# P06_LED_Config_Button.net
KiCad netlist of a schematic drawn in Altium Designer
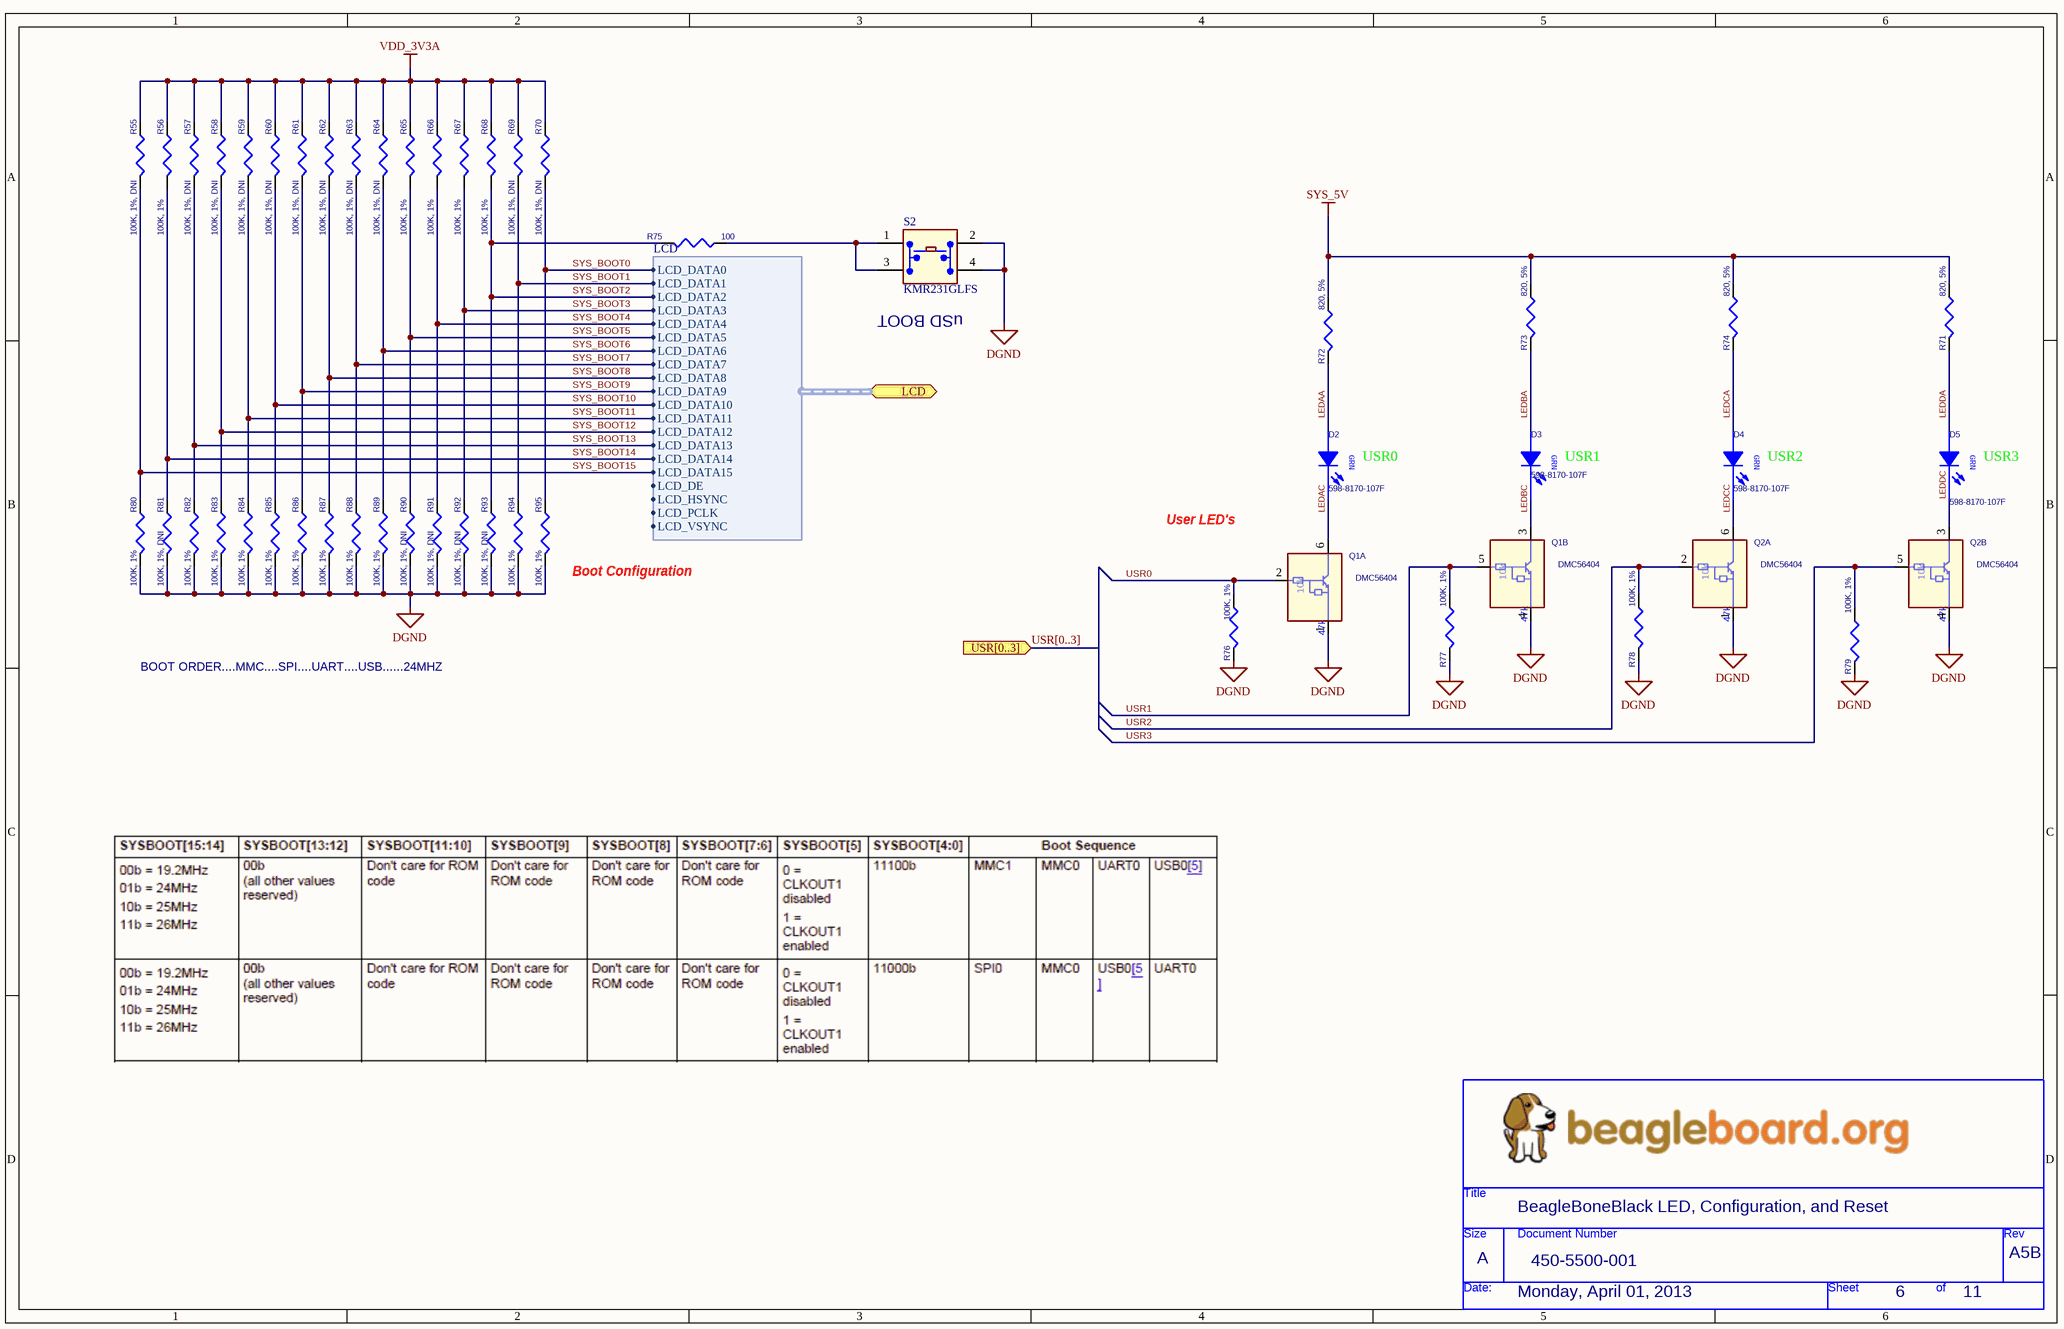
[diagram p0: P06_LED, Config, & Button.SchDoc]

(export (version "E")
  (design (tool "Eeschema 10.0.6"))
  (components
    (comp (ref "D2")
      (value "598-8170-107F")
      (footprint "LED_0603")
      (description "LED GREEN CLEAR 0805 SMD")
      (fields
        (field (name "MANUFACTURER") "Lite-On Inc")
        (field (name "MANUFACTURER PART NUMBER") "LTST-C170KGKT")
      )
      (libsource (lib "BEAGLEBONEBLACK_REV A5B") (part "LED_LTST-C150GKT"))
    )
    (comp (ref "D3")
      (value "598-8170-107F")
      (footprint "LED_0603")
      (description "LED GREEN CLEAR 0805 SMD")
      (fields
        (field (name "MANUFACTURER") "Lite-On Inc")
        (field (name "MANUFACTURER PART NUMBER") "LTST-C170KGKT")
      )
      (libsource (lib "BEAGLEBONEBLACK_REV A5B") (part "LED_LTST-C150GKT"))
    )
    (comp (ref "D4")
      (value "598-8170-107F")
      (footprint "LED_0603")
      (description "LED GREEN CLEAR 0805 SMD")
      (fields
        (field (name "MANUFACTURER") "Lite-On Inc")
        (field (name "MANUFACTURER PART NUMBER") "LTST-C170KGKT")
      )
      (libsource (lib "BEAGLEBONEBLACK_REV A5B") (part "LED_LTST-C150GKT"))
    )
    (comp (ref "D5")
      (value "598-8170-107F")
      (footprint "LED_0603")
      (description "LED GREEN CLEAR 0805 SMD")
      (fields
        (field (name "MANUFACTURER") "Lite-On Inc")
        (field (name "MANUFACTURER PART NUMBER") "LTST-C170KGKT")
      )
      (libsource (lib "BEAGLEBONEBLACK_REV A5B") (part "LED_LTST-C150GKT"))
    )
    (comp (ref "Q1")
      (value "DMC56404")
      (description "TRANS PREBIASED DUAL NPN SOT363")
      (fields
        (field (name "MANUFACTURER") "Toshiba")
        (field (name "MANUFACTURER PART NUMBER") "DDC114YU-7-F")
      )
      (libsource (lib "BEAGLEBONEBLACK_REV A5B") (part "RN1907"))
    )
    (comp (ref "Q2")
      (value "DMC56404")
      (description "TRANS PREBIASED DUAL NPN SOT363")
      (fields
        (field (name "MANUFACTURER") "Toshiba")
        (field (name "MANUFACTURER PART NUMBER") "DDC114YU-7-F")
      )
      (libsource (lib "BEAGLEBONEBLACK_REV A5B") (part "RN1907"))
    )
    (comp (ref "R55")
      (value "100K, 1%, DNI")
      (footprint "402")
      (description "RES 100K OHM 1/16W 1% 0402 SMD")
      (fields
        (field (name "MANUFACTURER") "Stackpole Electronics Inc")
        (field (name "MANUFACTURER PART NUMBER") "RMCF0402FT100K")
      )
      (libsource (lib "BEAGLEBONEBLACK_REV A5B") (part "RES_100K_1/16W_1%_0402"))
    )
    (comp (ref "R56")
      (value "100K, 1%")
      (footprint "402")
      (description "RES 100K OHM 1/16W 1% 0402 SMD")
      (fields
        (field (name "MANUFACTURER") "Stackpole Electronics Inc")
        (field (name "MANUFACTURER PART NUMBER") "RMCF0402FT100K")
      )
      (libsource (lib "BEAGLEBONEBLACK_REV A5B") (part "RES_100K_1/16W_1%_0402"))
    )
    (comp (ref "R57")
      (value "100K, 1%, DNI")
      (footprint "402")
      (description "RES 100K OHM 1/16W 1% 0402 SMD")
      (fields
        (field (name "MANUFACTURER") "Stackpole Electronics Inc")
        (field (name "MANUFACTURER PART NUMBER") "RMCF0402FT100K")
      )
      (libsource (lib "BEAGLEBONEBLACK_REV A5B") (part "RES_100K_1/16W_1%_0402"))
    )
    (comp (ref "R58")
      (value "100K, 1%, DNI")
      (footprint "402")
      (description "RES 100K OHM 1/16W 1% 0402 SMD")
      (fields
        (field (name "MANUFACTURER") "Stackpole Electronics Inc")
        (field (name "MANUFACTURER PART NUMBER") "RMCF0402FT100K")
      )
      (libsource (lib "BEAGLEBONEBLACK_REV A5B") (part "RES_100K_1/16W_1%_0402"))
    )
    (comp (ref "R59")
      (value "100K, 1%, DNI")
      (footprint "402")
      (description "RES 100K OHM 1/16W 1% 0402 SMD")
      (fields
        (field (name "MANUFACTURER") "Stackpole Electronics Inc")
        (field (name "MANUFACTURER PART NUMBER") "RMCF0402FT100K")
      )
      (libsource (lib "BEAGLEBONEBLACK_REV A5B") (part "RES_100K_1/16W_1%_0402"))
    )
    (comp (ref "R60")
      (value "100K, 1%, DNI")
      (footprint "402")
      (description "RES 100K OHM 1/16W 1% 0402 SMD")
      (fields
        (field (name "MANUFACTURER") "Stackpole Electronics Inc")
        (field (name "MANUFACTURER PART NUMBER") "RMCF0402FT100K")
      )
      (libsource (lib "BEAGLEBONEBLACK_REV A5B") (part "RES_100K_1/16W_1%_0402"))
    )
    (comp (ref "R61")
      (value "100K, 1%, DNI")
      (footprint "402")
      (description "RES 100K OHM 1/16W 1% 0402 SMD")
      (fields
        (field (name "MANUFACTURER") "Stackpole Electronics Inc")
        (field (name "MANUFACTURER PART NUMBER") "RMCF0402FT100K")
      )
      (libsource (lib "BEAGLEBONEBLACK_REV A5B") (part "RES_100K_1/16W_1%_0402"))
    )
    (comp (ref "R62")
      (value "100K, 1%, DNI")
      (footprint "402")
      (description "RES 100K OHM 1/16W 1% 0402 SMD")
      (fields
        (field (name "MANUFACTURER") "Stackpole Electronics Inc")
        (field (name "MANUFACTURER PART NUMBER") "RMCF0402FT100K")
      )
      (libsource (lib "BEAGLEBONEBLACK_REV A5B") (part "RES_100K_1/16W_1%_0402"))
    )
    (comp (ref "R63")
      (value "100K, 1%, DNI")
      (footprint "402")
      (description "RES 100K OHM 1/16W 1% 0402 SMD")
      (fields
        (field (name "MANUFACTURER") "Stackpole Electronics Inc")
        (field (name "MANUFACTURER PART NUMBER") "RMCF0402FT100K")
      )
      (libsource (lib "BEAGLEBONEBLACK_REV A5B") (part "RES_100K_1/16W_1%_0402"))
    )
    (comp (ref "R64")
      (value "100K, 1%, DNI")
      (footprint "402")
      (description "RES 100K OHM 1/16W 1% 0402 SMD")
      (fields
        (field (name "MANUFACTURER") "Stackpole Electronics Inc")
        (field (name "MANUFACTURER PART NUMBER") "RMCF0402FT100K")
      )
      (libsource (lib "BEAGLEBONEBLACK_REV A5B") (part "RES_100K_1/16W_1%_0402"))
    )
    (comp (ref "R65")
      (value "100K, 1%")
      (footprint "402")
      (description "RES 100K OHM 1/16W 1% 0402 SMD")
      (fields
        (field (name "MANUFACTURER") "Stackpole Electronics Inc")
        (field (name "MANUFACTURER PART NUMBER") "RMCF0402FT100K")
      )
      (libsource (lib "BEAGLEBONEBLACK_REV A5B") (part "RES_100K_1/16W_1%_0402"))
    )
    (comp (ref "R66")
      (value "100K, 1%")
      (footprint "402")
      (description "RES 100K OHM 1/16W 1% 0402 SMD")
      (fields
        (field (name "MANUFACTURER") "Stackpole Electronics Inc")
        (field (name "MANUFACTURER PART NUMBER") "RMCF0402FT100K")
      )
      (libsource (lib "BEAGLEBONEBLACK_REV A5B") (part "RES_100K_1/16W_1%_0402"))
    )
    (comp (ref "R67")
      (value "100K, 1%")
      (footprint "402")
      (description "RES 100K OHM 1/16W 1% 0402 SMD")
      (fields
        (field (name "MANUFACTURER") "Stackpole Electronics Inc")
        (field (name "MANUFACTURER PART NUMBER") "RMCF0402FT100K")
      )
      (libsource (lib "BEAGLEBONEBLACK_REV A5B") (part "RES_100K_1/16W_1%_0402"))
    )
    (comp (ref "R68")
      (value "100K, 1%")
      (footprint "402")
      (description "RES 100K OHM 1/16W 1% 0402 SMD")
      (fields
        (field (name "MANUFACTURER") "Stackpole Electronics Inc")
        (field (name "MANUFACTURER PART NUMBER") "RMCF0402FT100K")
      )
      (libsource (lib "BEAGLEBONEBLACK_REV A5B") (part "RES_100K_1/16W_1%_0402"))
    )
    (comp (ref "R69")
      (value "100K, 1%, DNI")
      (footprint "402")
      (description "RES 100K OHM 1/16W 1% 0402 SMD")
      (fields
        (field (name "MANUFACTURER") "Stackpole Electronics Inc")
        (field (name "MANUFACTURER PART NUMBER") "RMCF0402FT100K")
      )
      (libsource (lib "BEAGLEBONEBLACK_REV A5B") (part "RES_100K_1/16W_1%_0402"))
    )
    (comp (ref "R70")
      (value "100K, 1%, DNI")
      (footprint "402")
      (description "RES 100K OHM 1/16W 1% 0402 SMD")
      (fields
        (field (name "MANUFACTURER") "Stackpole Electronics Inc")
        (field (name "MANUFACTURER PART NUMBER") "RMCF0402FT100K")
      )
      (libsource (lib "BEAGLEBONEBLACK_REV A5B") (part "RES_100K_1/16W_1%_0402"))
    )
    (comp (ref "R71")
      (value "820, 5%")
      (footprint "402")
      (description "RES 820 OHM 1/10W 5% 0402 SMD")
      (fields
        (field (name "MANUFACTURER") "Yageo")
        (field (name "MANUFACTURER PART NUMBER") "RC0402JR-07820RL")
      )
      (libsource (lib "BEAGLEBONEBLACK_REV A5B") (part "RES_470_1/10W_5%_0402"))
    )
    (comp (ref "R72")
      (value "820, 5%")
      (footprint "402")
      (description "RES 820 OHM 1/10W 5% 0402 SMD")
      (fields
        (field (name "MANUFACTURER") "Yageo")
        (field (name "MANUFACTURER PART NUMBER") "RC0402JR-07820RL")
      )
      (libsource (lib "BEAGLEBONEBLACK_REV A5B") (part "RES_470_1/10W_5%_0402"))
    )
    (comp (ref "R73")
      (value "820, 5%")
      (footprint "402")
      (description "RES 820 OHM 1/10W 5% 0402 SMD")
      (fields
        (field (name "MANUFACTURER") "Yageo")
        (field (name "MANUFACTURER PART NUMBER") "RC0402JR-07820RL")
      )
      (libsource (lib "BEAGLEBONEBLACK_REV A5B") (part "RES_470_1/10W_5%_0402"))
    )
    (comp (ref "R74")
      (value "820, 5%")
      (footprint "402")
      (description "RES 820 OHM 1/10W 5% 0402 SMD")
      (fields
        (field (name "MANUFACTURER") "Yageo")
        (field (name "MANUFACTURER PART NUMBER") "RC0402JR-07820RL")
      )
      (libsource (lib "BEAGLEBONEBLACK_REV A5B") (part "RES_470_1/10W_5%_0402"))
    )
    (comp (ref "R75")
      (value "100")
      (footprint "402")
      (description "RES 100 OHM 1/10W 5% 0402 SMD")
      (fields
        (field (name "MANUFACTURER") "Panasonic Electronic Components")
        (field (name "MANUFACTURER PART NUMBER") "ERJ-2RKF1000X")
      )
      (libsource (lib "BEAGLEBONEBLACK_REV A5B") (part "RES SMD"))
    )
    (comp (ref "R76")
      (value "100K, 1%")
      (footprint "402")
      (description "RES 100K OHM 1/16W 1% 0402 SMD")
      (fields
        (field (name "MANUFACTURER") "Stackpole Electronics Inc")
        (field (name "MANUFACTURER PART NUMBER") "RMCF0402FT100K")
      )
      (libsource (lib "BEAGLEBONEBLACK_REV A5B") (part "RES_100K_1/16W_1%_0402"))
    )
    (comp (ref "R77")
      (value "100K, 1%")
      (footprint "402")
      (description "RES 100K OHM 1/16W 1% 0402 SMD")
      (fields
        (field (name "MANUFACTURER") "Stackpole Electronics Inc")
        (field (name "MANUFACTURER PART NUMBER") "RMCF0402FT100K")
      )
      (libsource (lib "BEAGLEBONEBLACK_REV A5B") (part "RES_100K_1/16W_1%_0402"))
    )
    (comp (ref "R78")
      (value "100K, 1%")
      (footprint "402")
      (description "RES 100K OHM 1/16W 1% 0402 SMD")
      (fields
        (field (name "MANUFACTURER") "Stackpole Electronics Inc")
        (field (name "MANUFACTURER PART NUMBER") "RMCF0402FT100K")
      )
      (libsource (lib "BEAGLEBONEBLACK_REV A5B") (part "RES_100K_1/16W_1%_0402"))
    )
    (comp (ref "R79")
      (value "100K, 1%")
      (footprint "402")
      (description "RES 100K OHM 1/16W 1% 0402 SMD")
      (fields
        (field (name "MANUFACTURER") "Stackpole Electronics Inc")
        (field (name "MANUFACTURER PART NUMBER") "RMCF0402FT100K")
      )
      (libsource (lib "BEAGLEBONEBLACK_REV A5B") (part "RES_100K_1/16W_1%_0402"))
    )
    (comp (ref "R80")
      (value "100K, 1%")
      (footprint "402")
      (description "RES 100K OHM 1/16W 1% 0402 SMD")
      (fields
        (field (name "MANUFACTURER") "Stackpole Electronics Inc")
        (field (name "MANUFACTURER PART NUMBER") "RMCF0402FT100K")
      )
      (libsource (lib "BEAGLEBONEBLACK_REV A5B") (part "RES_100K_1/16W_1%_0402"))
    )
    (comp (ref "R81")
      (value "100K, 1%, DNI")
      (footprint "402")
      (description "RES 100K OHM 1/16W 1% 0402 SMD")
      (fields
        (field (name "MANUFACTURER") "Stackpole Electronics Inc")
        (field (name "MANUFACTURER PART NUMBER") "RMCF0402FT100K")
      )
      (libsource (lib "BEAGLEBONEBLACK_REV A5B") (part "RES_100K_1/16W_1%_0402"))
    )
    (comp (ref "R82")
      (value "100K, 1%")
      (footprint "402")
      (description "RES 100K OHM 1/16W 1% 0402 SMD")
      (fields
        (field (name "MANUFACTURER") "Stackpole Electronics Inc")
        (field (name "MANUFACTURER PART NUMBER") "RMCF0402FT100K")
      )
      (libsource (lib "BEAGLEBONEBLACK_REV A5B") (part "RES_100K_1/16W_1%_0402"))
    )
    (comp (ref "R83")
      (value "100K, 1%")
      (footprint "402")
      (description "RES 100K OHM 1/16W 1% 0402 SMD")
      (fields
        (field (name "MANUFACTURER") "Stackpole Electronics Inc")
        (field (name "MANUFACTURER PART NUMBER") "RMCF0402FT100K")
      )
      (libsource (lib "BEAGLEBONEBLACK_REV A5B") (part "RES_100K_1/16W_1%_0402"))
    )
    (comp (ref "R84")
      (value "100K, 1%")
      (footprint "402")
      (description "RES 100K OHM 1/16W 1% 0402 SMD")
      (fields
        (field (name "MANUFACTURER") "Stackpole Electronics Inc")
        (field (name "MANUFACTURER PART NUMBER") "RMCF0402FT100K")
      )
      (libsource (lib "BEAGLEBONEBLACK_REV A5B") (part "RES_100K_1/16W_1%_0402"))
    )
    (comp (ref "R85")
      (value "100K, 1%")
      (footprint "402")
      (description "RES 100K OHM 1/16W 1% 0402 SMD")
      (fields
        (field (name "MANUFACTURER") "Stackpole Electronics Inc")
        (field (name "MANUFACTURER PART NUMBER") "RMCF0402FT100K")
      )
      (libsource (lib "BEAGLEBONEBLACK_REV A5B") (part "RES_100K_1/16W_1%_0402"))
    )
    (comp (ref "R86")
      (value "100K, 1%")
      (footprint "402")
      (description "RES 100K OHM 1/16W 1% 0402 SMD")
      (fields
        (field (name "MANUFACTURER") "Stackpole Electronics Inc")
        (field (name "MANUFACTURER PART NUMBER") "RMCF0402FT100K")
      )
      (libsource (lib "BEAGLEBONEBLACK_REV A5B") (part "RES_100K_1/16W_1%_0402"))
    )
    (comp (ref "R87")
      (value "100K, 1%")
      (footprint "402")
      (description "RES 100K OHM 1/16W 1% 0402 SMD")
      (fields
        (field (name "MANUFACTURER") "Stackpole Electronics Inc")
        (field (name "MANUFACTURER PART NUMBER") "RMCF0402FT100K")
      )
      (libsource (lib "BEAGLEBONEBLACK_REV A5B") (part "RES_100K_1/16W_1%_0402"))
    )
    (comp (ref "R88")
      (value "100K, 1%")
      (footprint "402")
      (description "RES 100K OHM 1/16W 1% 0402 SMD")
      (fields
        (field (name "MANUFACTURER") "Stackpole Electronics Inc")
        (field (name "MANUFACTURER PART NUMBER") "RMCF0402FT100K")
      )
      (libsource (lib "BEAGLEBONEBLACK_REV A5B") (part "RES_100K_1/16W_1%_0402"))
    )
    (comp (ref "R89")
      (value "100K, 1%")
      (footprint "402")
      (description "RES 100K OHM 1/16W 1% 0402 SMD")
      (fields
        (field (name "MANUFACTURER") "Stackpole Electronics Inc")
        (field (name "MANUFACTURER PART NUMBER") "RMCF0402FT100K")
      )
      (libsource (lib "BEAGLEBONEBLACK_REV A5B") (part "RES_100K_1/16W_1%_0402"))
    )
    (comp (ref "R90")
      (value "100K, 1%, DNI")
      (footprint "402")
      (description "RES 100K OHM 1/16W 1% 0402 SMD")
      (fields
        (field (name "MANUFACTURER") "Stackpole Electronics Inc")
        (field (name "MANUFACTURER PART NUMBER") "RMCF0402FT100K")
      )
      (libsource (lib "BEAGLEBONEBLACK_REV A5B") (part "RES_100K_1/16W_1%_0402"))
    )
    (comp (ref "R91")
      (value "100K, 1%, DNI")
      (footprint "402")
      (description "RES 100K OHM 1/16W 1% 0402 SMD")
      (fields
        (field (name "MANUFACTURER") "Stackpole Electronics Inc")
        (field (name "MANUFACTURER PART NUMBER") "RMCF0402FT100K")
      )
      (libsource (lib "BEAGLEBONEBLACK_REV A5B") (part "RES_100K_1/16W_1%_0402"))
    )
    (comp (ref "R92")
      (value "100K, 1%, DNI")
      (footprint "402")
      (description "RES 100K OHM 1/16W 1% 0402 SMD")
      (fields
        (field (name "MANUFACTURER") "Stackpole Electronics Inc")
        (field (name "MANUFACTURER PART NUMBER") "RMCF0402FT100K")
      )
      (libsource (lib "BEAGLEBONEBLACK_REV A5B") (part "RES_100K_1/16W_1%_0402"))
    )
    (comp (ref "R93")
      (value "100K, 1%, DNI")
      (footprint "402")
      (description "RES 100K OHM 1/16W 1% 0402 SMD")
      (fields
        (field (name "MANUFACTURER") "Stackpole Electronics Inc")
        (field (name "MANUFACTURER PART NUMBER") "RMCF0402FT100K")
      )
      (libsource (lib "BEAGLEBONEBLACK_REV A5B") (part "RES_100K_1/16W_1%_0402"))
    )
    (comp (ref "R94")
      (value "100K, 1%")
      (footprint "402")
      (description "RES 100K OHM 1/16W 1% 0402 SMD")
      (fields
        (field (name "MANUFACTURER") "Stackpole Electronics Inc")
        (field (name "MANUFACTURER PART NUMBER") "RMCF0402FT100K")
      )
      (libsource (lib "BEAGLEBONEBLACK_REV A5B") (part "RES_100K_1/16W_1%_0402"))
    )
    (comp (ref "R95")
      (value "100K, 1%")
      (footprint "402")
      (description "RES 100K OHM 1/16W 1% 0402 SMD")
      (fields
        (field (name "MANUFACTURER") "Stackpole Electronics Inc")
        (field (name "MANUFACTURER PART NUMBER") "RMCF0402FT100K")
      )
      (libsource (lib "BEAGLEBONEBLACK_REV A5B") (part "RES_100K_1/16W_1%_0402"))
    )
    (comp (ref "S2")
      (value "KMR231GLFS")
      (footprint "SW4SMD_63X161LS")
      (description "Microminiature Tact Switch for SMT")
      (fields (field (name "MANUFACTURER") "C&K Components"))
      (libsource (lib "BEAGLEBONEBLACK_REV A5B") (part "KMR2"))
    )
  )
  (nets
    (net (code "2") (name "/LEDAA") (class "Default")
      (node (ref "D2") (pin "2") (pinfunction "A_2") (pintype "passive"))
      (node (ref "R72") (pin "2") (pinfunction "2_2") (pintype "passive"))
    )
    (net (code "3") (name "/LEDAC") (class "Default")
      (node (ref "D2") (pin "1") (pinfunction "C_1") (pintype "passive"))
      (node (ref "Q1") (pin "6") (pinfunction "3_6") (pintype "passive"))
    )
    (net (code "4") (name "/LEDBA") (class "Default")
      (node (ref "D3") (pin "2") (pinfunction "A_2") (pintype "passive"))
      (node (ref "R73") (pin "2") (pinfunction "2_2") (pintype "passive"))
    )
    (net (code "5") (name "/LEDBC") (class "Default")
      (node (ref "D3") (pin "1") (pinfunction "C_1") (pintype "passive"))
      (node (ref "Q1") (pin "3") (pinfunction "3_3") (pintype "passive"))
    )
    (net (code "6") (name "/LEDCA") (class "Default")
      (node (ref "D4") (pin "2") (pinfunction "A_2") (pintype "passive"))
      (node (ref "R74") (pin "2") (pinfunction "2_2") (pintype "passive"))
    )
    (net (code "7") (name "/LEDCC") (class "Default")
      (node (ref "D4") (pin "1") (pinfunction "C_1") (pintype "passive"))
      (node (ref "Q2") (pin "6") (pinfunction "3_6") (pintype "passive"))
    )
    (net (code "8") (name "/LEDDA") (class "Default")
      (node (ref "D5") (pin "2") (pinfunction "A_2") (pintype "passive"))
      (node (ref "R71") (pin "2") (pinfunction "2_2") (pintype "passive"))
    )
    (net (code "9") (name "/LEDDC") (class "Default")
      (node (ref "D5") (pin "1") (pinfunction "C_1") (pintype "passive"))
      (node (ref "Q2") (pin "3") (pinfunction "3_3") (pintype "passive"))
    )
    (net (code "10") (name "/SYS_BOOT0") (class "Default")
      (node (ref "R70") (pin "2") (pinfunction "2_2") (pintype "passive"))
      (node (ref "R95") (pin "1") (pinfunction "1_1") (pintype "passive"))
    )
    (net (code "11") (name "/SYS_BOOT1") (class "Default")
      (node (ref "R69") (pin "2") (pinfunction "2_2") (pintype "passive"))
      (node (ref "R94") (pin "1") (pinfunction "1_1") (pintype "passive"))
    )
    (net (code "12") (name "/SYS_BOOT2") (class "Default")
      (node (ref "R68") (pin "2") (pinfunction "2_2") (pintype "passive"))
      (node (ref "R75") (pin "1") (pinfunction "P1_1") (pintype "passive"))
      (node (ref "R93") (pin "1") (pinfunction "1_1") (pintype "passive"))
    )
    (net (code "13") (name "/SYS_BOOT3") (class "Default")
      (node (ref "R67") (pin "2") (pinfunction "2_2") (pintype "passive"))
      (node (ref "R92") (pin "1") (pinfunction "1_1") (pintype "passive"))
    )
    (net (code "14") (name "/SYS_BOOT4") (class "Default")
      (node (ref "R66") (pin "2") (pinfunction "2_2") (pintype "passive"))
      (node (ref "R91") (pin "1") (pinfunction "1_1") (pintype "passive"))
    )
    (net (code "15") (name "/SYS_BOOT5") (class "Default")
      (node (ref "R65") (pin "2") (pinfunction "2_2") (pintype "passive"))
      (node (ref "R90") (pin "1") (pinfunction "1_1") (pintype "passive"))
    )
    (net (code "16") (name "/SYS_BOOT6") (class "Default")
      (node (ref "R64") (pin "2") (pinfunction "2_2") (pintype "passive"))
      (node (ref "R89") (pin "1") (pinfunction "1_1") (pintype "passive"))
    )
    (net (code "17") (name "/SYS_BOOT7") (class "Default")
      (node (ref "R63") (pin "2") (pinfunction "2_2") (pintype "passive"))
      (node (ref "R88") (pin "1") (pinfunction "1_1") (pintype "passive"))
    )
    (net (code "18") (name "/SYS_BOOT8") (class "Default")
      (node (ref "R62") (pin "2") (pinfunction "2_2") (pintype "passive"))
      (node (ref "R87") (pin "1") (pinfunction "1_1") (pintype "passive"))
    )
    (net (code "19") (name "/SYS_BOOT9") (class "Default")
      (node (ref "R61") (pin "2") (pinfunction "2_2") (pintype "passive"))
      (node (ref "R86") (pin "1") (pinfunction "1_1") (pintype "passive"))
    )
    (net (code "20") (name "/SYS_BOOT10") (class "Default")
      (node (ref "R60") (pin "2") (pinfunction "2_2") (pintype "passive"))
      (node (ref "R85") (pin "1") (pinfunction "1_1") (pintype "passive"))
    )
    (net (code "21") (name "/SYS_BOOT11") (class "Default")
      (node (ref "R59") (pin "2") (pinfunction "2_2") (pintype "passive"))
      (node (ref "R84") (pin "1") (pinfunction "1_1") (pintype "passive"))
    )
    (net (code "22") (name "/SYS_BOOT12") (class "Default")
      (node (ref "R58") (pin "2") (pinfunction "2_2") (pintype "passive"))
      (node (ref "R83") (pin "1") (pinfunction "1_1") (pintype "passive"))
    )
    (net (code "23") (name "/SYS_BOOT13") (class "Default")
      (node (ref "R57") (pin "2") (pinfunction "2_2") (pintype "passive"))
      (node (ref "R82") (pin "1") (pinfunction "1_1") (pintype "passive"))
    )
    (net (code "24") (name "/SYS_BOOT14") (class "Default")
      (node (ref "R56") (pin "2") (pinfunction "2_2") (pintype "passive"))
      (node (ref "R81") (pin "1") (pinfunction "1_1") (pintype "passive"))
    )
    (net (code "25") (name "/SYS_BOOT15") (class "Default")
      (node (ref "R55") (pin "2") (pinfunction "2_2") (pintype "passive"))
      (node (ref "R80") (pin "1") (pinfunction "1_1") (pintype "passive"))
    )
    (net (code "26") (name "/USR0") (class "Default")
      (node (ref "Q1") (pin "2") (pinfunction "5_2") (pintype "passive"))
      (node (ref "R76") (pin "1") (pinfunction "1_1") (pintype "passive"))
    )
    (net (code "27") (name "/USR1") (class "Default")
      (node (ref "Q1") (pin "5") (pinfunction "5_5") (pintype "passive"))
      (node (ref "R77") (pin "1") (pinfunction "1_1") (pintype "passive"))
    )
    (net (code "28") (name "/USR2") (class "Default")
      (node (ref "Q2") (pin "2") (pinfunction "5_2") (pintype "passive"))
      (node (ref "R78") (pin "1") (pinfunction "1_1") (pintype "passive"))
    )
    (net (code "29") (name "/USR3") (class "Default")
      (node (ref "Q2") (pin "5") (pinfunction "5_5") (pintype "passive"))
      (node (ref "R79") (pin "1") (pinfunction "1_1") (pintype "passive"))
    )
    (net (code "32") (name "DGND") (class "Default")
      (node (ref "Q1") (pin "1") (pinfunction "4_1") (pintype "passive"))
      (node (ref "Q1") (pin "4") (pinfunction "4_4") (pintype "passive"))
      (node (ref "Q2") (pin "1") (pinfunction "4_1") (pintype "passive"))
      (node (ref "Q2") (pin "4") (pinfunction "4_4") (pintype "passive"))
      (node (ref "R76") (pin "2") (pinfunction "2_2") (pintype "passive"))
      (node (ref "R77") (pin "2") (pinfunction "2_2") (pintype "passive"))
      (node (ref "R78") (pin "2") (pinfunction "2_2") (pintype "passive"))
      (node (ref "R79") (pin "2") (pinfunction "2_2") (pintype "passive"))
      (node (ref "R80") (pin "2") (pinfunction "2_2") (pintype "passive"))
      (node (ref "R81") (pin "2") (pinfunction "2_2") (pintype "passive"))
      (node (ref "R82") (pin "2") (pinfunction "2_2") (pintype "passive"))
      (node (ref "R83") (pin "2") (pinfunction "2_2") (pintype "passive"))
      (node (ref "R84") (pin "2") (pinfunction "2_2") (pintype "passive"))
      (node (ref "R85") (pin "2") (pinfunction "2_2") (pintype "passive"))
      (node (ref "R86") (pin "2") (pinfunction "2_2") (pintype "passive"))
      (node (ref "R87") (pin "2") (pinfunction "2_2") (pintype "passive"))
      (node (ref "R88") (pin "2") (pinfunction "2_2") (pintype "passive"))
      (node (ref "R89") (pin "2") (pinfunction "2_2") (pintype "passive"))
      (node (ref "R90") (pin "2") (pinfunction "2_2") (pintype "passive"))
      (node (ref "R91") (pin "2") (pinfunction "2_2") (pintype "passive"))
      (node (ref "R92") (pin "2") (pinfunction "2_2") (pintype "passive"))
      (node (ref "R93") (pin "2") (pinfunction "2_2") (pintype "passive"))
      (node (ref "R94") (pin "2") (pinfunction "2_2") (pintype "passive"))
      (node (ref "R95") (pin "2") (pinfunction "2_2") (pintype "passive"))
      (node (ref "S2") (pin "2") (pinfunction "A2_2") (pintype "passive"))
      (node (ref "S2") (pin "4") (pinfunction "4_4") (pintype "power_in"))
    )
    (net (code "33") (name "Net-(R75-P2)") (class "Default")
      (node (ref "R75") (pin "2") (pinfunction "P2_2") (pintype "passive"))
      (node (ref "S2") (pin "1") (pinfunction "A1_1") (pintype "passive"))
      (node (ref "S2") (pin "3") (pinfunction "A3_3") (pintype "passive"))
    )
    (net (code "34") (name "SYS_5V") (class "Default")
      (node (ref "R71") (pin "1") (pinfunction "1_1") (pintype "passive"))
      (node (ref "R72") (pin "1") (pinfunction "1_1") (pintype "passive"))
      (node (ref "R73") (pin "1") (pinfunction "1_1") (pintype "passive"))
      (node (ref "R74") (pin "1") (pinfunction "1_1") (pintype "passive"))
    )
    (net (code "35") (name "VDD_3V3A") (class "Default")
      (node (ref "R55") (pin "1") (pinfunction "1_1") (pintype "passive"))
      (node (ref "R56") (pin "1") (pinfunction "1_1") (pintype "passive"))
      (node (ref "R57") (pin "1") (pinfunction "1_1") (pintype "passive"))
      (node (ref "R58") (pin "1") (pinfunction "1_1") (pintype "passive"))
      (node (ref "R59") (pin "1") (pinfunction "1_1") (pintype "passive"))
      (node (ref "R60") (pin "1") (pinfunction "1_1") (pintype "passive"))
      (node (ref "R61") (pin "1") (pinfunction "1_1") (pintype "passive"))
      (node (ref "R62") (pin "1") (pinfunction "1_1") (pintype "passive"))
      (node (ref "R63") (pin "1") (pinfunction "1_1") (pintype "passive"))
      (node (ref "R64") (pin "1") (pinfunction "1_1") (pintype "passive"))
      (node (ref "R65") (pin "1") (pinfunction "1_1") (pintype "passive"))
      (node (ref "R66") (pin "1") (pinfunction "1_1") (pintype "passive"))
      (node (ref "R67") (pin "1") (pinfunction "1_1") (pintype "passive"))
      (node (ref "R68") (pin "1") (pinfunction "1_1") (pintype "passive"))
      (node (ref "R69") (pin "1") (pinfunction "1_1") (pintype "passive"))
      (node (ref "R70") (pin "1") (pinfunction "1_1") (pintype "passive"))
    )
  )
)
